# edge_dff_drafts.net
KiCad netlist of a schematic drawn in Altium Designer
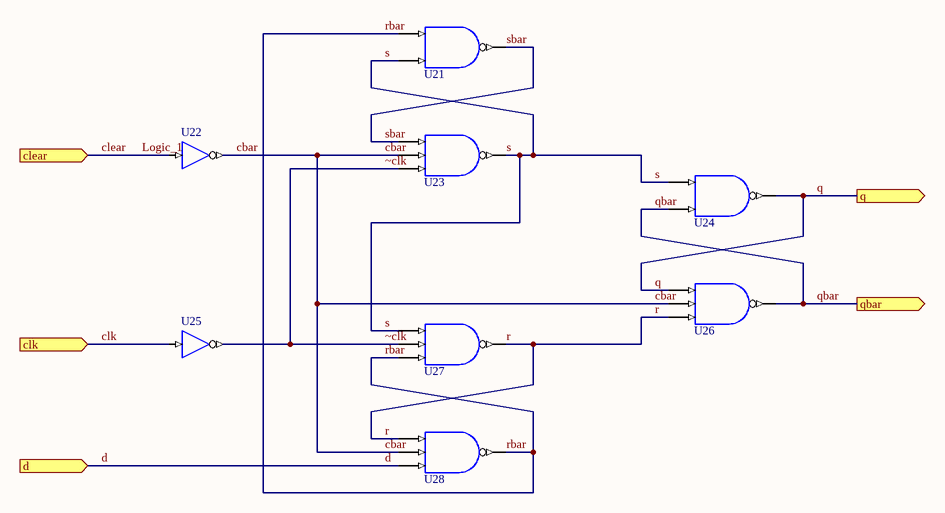
[diagram p0: edge_dff_drafts.SchDoc]

(export (version "E")
  (design (tool "Eeschema 10.0.6"))
  (components
    (comp (ref "U21")
      (value "AND 2")
      (description "2 Input AND")
      (libsource (lib "BlockSchematics") (part "AND_2"))
    )
    (comp (ref "U22")
      (value "BUF_inv")
      (description "1-bit General Purpose (Non-inverting) Buffer")
      (libsource (lib "BlockSchematics") (part "BUF_inv"))
    )
    (comp (ref "U23")
      (value "NAND_3")
      (description "3 Input NAND 1 Not")
      (libsource (lib "BlockSchematics") (part "NAND_3"))
    )
    (comp (ref "U24")
      (value "AND 2")
      (description "2 Input AND")
      (libsource (lib "BlockSchematics") (part "AND_2"))
    )
    (comp (ref "U25")
      (value "BUF_inv")
      (description "1-bit General Purpose (Non-inverting) Buffer")
      (libsource (lib "BlockSchematics") (part "BUF_inv"))
    )
    (comp (ref "U26")
      (value "NAND_3")
      (description "3 Input NAND 1 Not")
      (libsource (lib "BlockSchematics") (part "NAND_3"))
    )
    (comp (ref "U27")
      (value "NAND_3")
      (description "3 Input NAND 1 Not")
      (libsource (lib "BlockSchematics") (part "NAND_3"))
    )
    (comp (ref "U28")
      (value "NAND_3")
      (description "3 Input NAND 1 Not")
      (libsource (lib "BlockSchematics") (part "NAND_3"))
    )
  )
  (nets
    (net (code "1") (name "/Logic_1") (class "Default")
      (node (ref "U22") (pin "I") (pinfunction "I_I") (pintype "input"))
    )
    (net (code "2") (name "/cbar") (class "Default")
      (node (ref "U22") (pin "O") (pinfunction "O_O") (pintype "output"))
      (node (ref "U23") (pin "B") (pinfunction "B_B") (pintype "input"))
      (node (ref "U26") (pin "B") (pinfunction "B_B") (pintype "input"))
      (node (ref "U28") (pin "B") (pinfunction "B_B") (pintype "input"))
    )
    (net (code "3") (name "/clk") (class "Default")
      (node (ref "U25") (pin "I") (pinfunction "I_I") (pintype "input"))
    )
    (net (code "4") (name "/d") (class "Default")
      (node (ref "U28") (pin "C") (pinfunction "C_C") (pintype "input"))
    )
    (net (code "5") (name "/q") (class "Default")
      (node (ref "U24") (pin "Y") (pinfunction "Y_Y") (pintype "output"))
      (node (ref "U26") (pin "A") (pinfunction "A_A") (pintype "input"))
    )
    (net (code "6") (name "/qbar") (class "Default")
      (node (ref "U24") (pin "B") (pinfunction "B_B") (pintype "input"))
      (node (ref "U26") (pin "Y") (pinfunction "Y_Y") (pintype "output"))
    )
    (net (code "7") (name "/r") (class "Default")
      (node (ref "U26") (pin "C") (pinfunction "C_C") (pintype "input"))
      (node (ref "U27") (pin "Y") (pinfunction "Y_Y") (pintype "output"))
      (node (ref "U28") (pin "A") (pinfunction "A_A") (pintype "input"))
    )
    (net (code "8") (name "/rbar") (class "Default")
      (node (ref "U21") (pin "A") (pinfunction "A_A") (pintype "input"))
      (node (ref "U27") (pin "C") (pinfunction "C_C") (pintype "input"))
      (node (ref "U28") (pin "Y") (pinfunction "Y_Y") (pintype "output"))
    )
    (net (code "9") (name "/s") (class "Default")
      (node (ref "U21") (pin "B") (pinfunction "B_B") (pintype "input"))
      (node (ref "U23") (pin "Y") (pinfunction "Y_Y") (pintype "output"))
      (node (ref "U24") (pin "A") (pinfunction "A_A") (pintype "input"))
      (node (ref "U27") (pin "A") (pinfunction "A_A") (pintype "input"))
    )
    (net (code "10") (name "/sbar") (class "Default")
      (node (ref "U21") (pin "Y") (pinfunction "Y_Y") (pintype "output"))
      (node (ref "U23") (pin "A") (pinfunction "A_A") (pintype "input"))
    )
    (net (code "11") (name "/~clk") (class "Default")
      (node (ref "U23") (pin "C") (pinfunction "C_C") (pintype "input"))
      (node (ref "U25") (pin "O") (pinfunction "O_O") (pintype "output"))
      (node (ref "U27") (pin "B") (pinfunction "B_B") (pintype "input"))
    )
  )
)
